# sch.net
KiCad netlist of a schematic drawn in Altium Designer
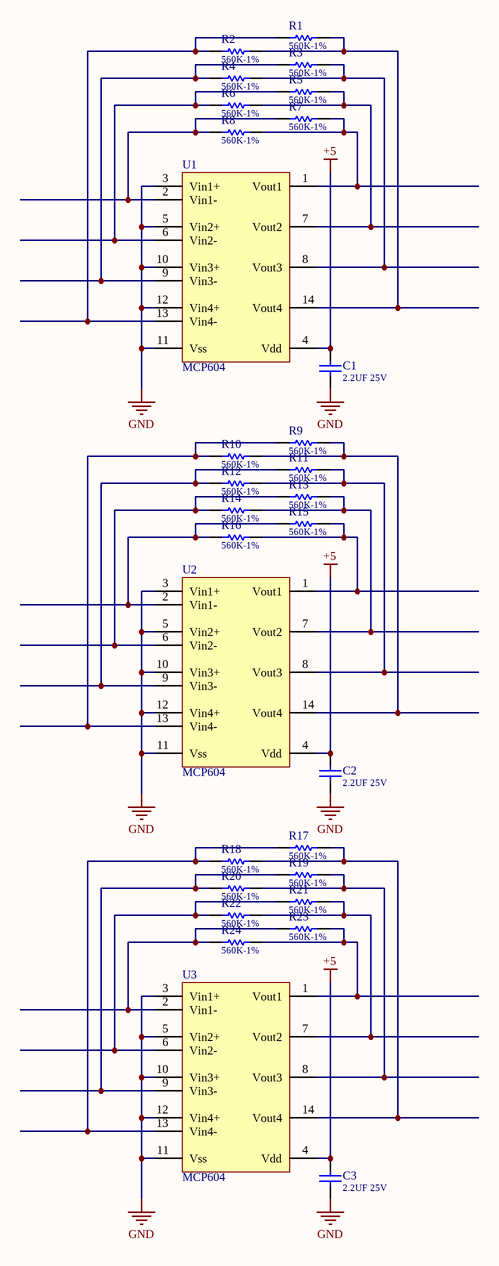
[diagram p0: sch.SchDoc]

(export (version "E")
  (design (tool "Eeschema 10.0.6"))
  (components
    (comp (ref "C1")
      (value "2.2UF 25V")
      (footprint "RC_0603")
      (fields (field (name "PART NUMBER") "CAP_0603_2.2UF 25V") (field (name "MANUFACTURER") "Murata"))
      (libsource (lib "RR_Passive") (part "CAP"))
    )
    (comp (ref "C2")
      (value "2.2UF 25V")
      (footprint "RC_0603")
      (fields (field (name "PART NUMBER") "CAP_0603_2.2UF 25V") (field (name "MANUFACTURER") "Murata"))
      (libsource (lib "RR_Passive") (part "CAP"))
    )
    (comp (ref "C3")
      (value "2.2UF 25V")
      (footprint "RC_0603")
      (fields (field (name "PART NUMBER") "CAP_0603_2.2UF 25V") (field (name "MANUFACTURER") "Murata"))
      (libsource (lib "RR_Passive") (part "CAP"))
    )
    (comp (ref "R1")
      (value "560K-1%")
      (footprint "RR_0603")
      (fields (field (name "MANUFACTURER") "Yageo"))
      (libsource (lib "RozumLibrary") (part "RES"))
    )
    (comp (ref "R2")
      (value "560K-1%")
      (footprint "RR_0603")
      (fields (field (name "MANUFACTURER") "Yageo"))
      (libsource (lib "RozumLibrary") (part "RES"))
    )
    (comp (ref "R3")
      (value "560K-1%")
      (footprint "RR_0603")
      (fields (field (name "MANUFACTURER") "Yageo"))
      (libsource (lib "RozumLibrary") (part "RES"))
    )
    (comp (ref "R4")
      (value "560K-1%")
      (footprint "RR_0603")
      (fields (field (name "MANUFACTURER") "Yageo"))
      (libsource (lib "RozumLibrary") (part "RES"))
    )
    (comp (ref "R5")
      (value "560K-1%")
      (footprint "RR_0603")
      (fields (field (name "MANUFACTURER") "Yageo"))
      (libsource (lib "RozumLibrary") (part "RES"))
    )
    (comp (ref "R6")
      (value "560K-1%")
      (footprint "RR_0603")
      (fields (field (name "MANUFACTURER") "Yageo"))
      (libsource (lib "RozumLibrary") (part "RES"))
    )
    (comp (ref "R7")
      (value "560K-1%")
      (footprint "RR_0603")
      (fields (field (name "MANUFACTURER") "Yageo"))
      (libsource (lib "RozumLibrary") (part "RES"))
    )
    (comp (ref "R8")
      (value "560K-1%")
      (footprint "RR_0603")
      (fields (field (name "MANUFACTURER") "Yageo"))
      (libsource (lib "RozumLibrary") (part "RES"))
    )
    (comp (ref "R9")
      (value "560K-1%")
      (footprint "RR_0603")
      (fields (field (name "MANUFACTURER") "Yageo"))
      (libsource (lib "RozumLibrary") (part "RES"))
    )
    (comp (ref "R10")
      (value "560K-1%")
      (footprint "RR_0603")
      (fields (field (name "MANUFACTURER") "Yageo"))
      (libsource (lib "RozumLibrary") (part "RES"))
    )
    (comp (ref "R11")
      (value "560K-1%")
      (footprint "RR_0603")
      (fields (field (name "MANUFACTURER") "Yageo"))
      (libsource (lib "RozumLibrary") (part "RES"))
    )
    (comp (ref "R12")
      (value "560K-1%")
      (footprint "RR_0603")
      (fields (field (name "MANUFACTURER") "Yageo"))
      (libsource (lib "RozumLibrary") (part "RES"))
    )
    (comp (ref "R13")
      (value "560K-1%")
      (footprint "RR_0603")
      (fields (field (name "MANUFACTURER") "Yageo"))
      (libsource (lib "RozumLibrary") (part "RES"))
    )
    (comp (ref "R14")
      (value "560K-1%")
      (footprint "RR_0603")
      (fields (field (name "MANUFACTURER") "Yageo"))
      (libsource (lib "RozumLibrary") (part "RES"))
    )
    (comp (ref "R15")
      (value "560K-1%")
      (footprint "RR_0603")
      (fields (field (name "MANUFACTURER") "Yageo"))
      (libsource (lib "RozumLibrary") (part "RES"))
    )
    (comp (ref "R16")
      (value "560K-1%")
      (footprint "RR_0603")
      (fields (field (name "MANUFACTURER") "Yageo"))
      (libsource (lib "RozumLibrary") (part "RES"))
    )
    (comp (ref "R17")
      (value "560K-1%")
      (footprint "RR_0603")
      (fields (field (name "MANUFACTURER") "Yageo"))
      (libsource (lib "RozumLibrary") (part "RES"))
    )
    (comp (ref "R18")
      (value "560K-1%")
      (footprint "RR_0603")
      (fields (field (name "MANUFACTURER") "Yageo"))
      (libsource (lib "RozumLibrary") (part "RES"))
    )
    (comp (ref "R19")
      (value "560K-1%")
      (footprint "RR_0603")
      (fields (field (name "MANUFACTURER") "Yageo"))
      (libsource (lib "RozumLibrary") (part "RES"))
    )
    (comp (ref "R20")
      (value "560K-1%")
      (footprint "RR_0603")
      (fields (field (name "MANUFACTURER") "Yageo"))
      (libsource (lib "RozumLibrary") (part "RES"))
    )
    (comp (ref "R21")
      (value "560K-1%")
      (footprint "RR_0603")
      (fields (field (name "MANUFACTURER") "Yageo"))
      (libsource (lib "RozumLibrary") (part "RES"))
    )
    (comp (ref "R22")
      (value "560K-1%")
      (footprint "RR_0603")
      (fields (field (name "MANUFACTURER") "Yageo"))
      (libsource (lib "RozumLibrary") (part "RES"))
    )
    (comp (ref "R23")
      (value "560K-1%")
      (footprint "RR_0603")
      (fields (field (name "MANUFACTURER") "Yageo"))
      (libsource (lib "RozumLibrary") (part "RES"))
    )
    (comp (ref "R24")
      (value "560K-1%")
      (footprint "RR_0603")
      (fields (field (name "MANUFACTURER") "Yageo"))
      (libsource (lib "RozumLibrary") (part "RES"))
    )
    (comp (ref "U1") (value "MCP604") (footprint "RR_SO14") (libsource (lib "lib") (part "MCP604")))
    (comp (ref "U2") (value "MCP604") (footprint "RR_SO14") (libsource (lib "lib") (part "MCP604")))
    (comp (ref "U3") (value "MCP604") (footprint "RR_SO14") (libsource (lib "lib") (part "MCP604")))
  )
  (nets
    (net (code "1") (name "+5") (class "Default")
      (node (ref "C1") (pin "2") (pinfunction "2_2") (pintype "passive"))
      (node (ref "C2") (pin "2") (pinfunction "2_2") (pintype "passive"))
      (node (ref "C3") (pin "2") (pinfunction "2_2") (pintype "passive"))
      (node (ref "U1") (pin "4") (pinfunction "Vdd_4") (pintype "passive"))
      (node (ref "U2") (pin "4") (pinfunction "Vdd_4") (pintype "passive"))
      (node (ref "U3") (pin "4") (pinfunction "Vdd_4") (pintype "passive"))
    )
    (net (code "2") (name "GND") (class "Default")
      (node (ref "C1") (pin "1") (pinfunction "1_1") (pintype "passive"))
      (node (ref "C2") (pin "1") (pinfunction "1_1") (pintype "passive"))
      (node (ref "C3") (pin "1") (pinfunction "1_1") (pintype "passive"))
      (node (ref "U1") (pin "10") (pinfunction "Vin3+_10") (pintype "passive"))
      (node (ref "U1") (pin "11") (pinfunction "Vss_11") (pintype "passive"))
      (node (ref "U1") (pin "12") (pinfunction "Vin4+_12") (pintype "passive"))
      (node (ref "U1") (pin "3") (pinfunction "Vin1+_3") (pintype "passive"))
      (node (ref "U1") (pin "5") (pinfunction "Vin2+_5") (pintype "passive"))
      (node (ref "U2") (pin "10") (pinfunction "Vin3+_10") (pintype "passive"))
      (node (ref "U2") (pin "11") (pinfunction "Vss_11") (pintype "passive"))
      (node (ref "U2") (pin "12") (pinfunction "Vin4+_12") (pintype "passive"))
      (node (ref "U2") (pin "3") (pinfunction "Vin1+_3") (pintype "passive"))
      (node (ref "U2") (pin "5") (pinfunction "Vin2+_5") (pintype "passive"))
      (node (ref "U3") (pin "10") (pinfunction "Vin3+_10") (pintype "passive"))
      (node (ref "U3") (pin "11") (pinfunction "Vss_11") (pintype "passive"))
      (node (ref "U3") (pin "12") (pinfunction "Vin4+_12") (pintype "passive"))
      (node (ref "U3") (pin "3") (pinfunction "Vin1+_3") (pintype "passive"))
      (node (ref "U3") (pin "5") (pinfunction "Vin2+_5") (pintype "passive"))
    )
    (net (code "3") (name "Net-(U1-Vin1-)") (class "Default")
      (node (ref "R7") (pin "2") (pinfunction "2_2") (pintype "passive"))
      (node (ref "R8") (pin "2") (pinfunction "2_2") (pintype "passive"))
      (node (ref "U1") (pin "2") (pinfunction "Vin1-_2") (pintype "passive"))
    )
    (net (code "4") (name "Net-(U1-Vin2-)") (class "Default")
      (node (ref "R5") (pin "2") (pinfunction "2_2") (pintype "passive"))
      (node (ref "R6") (pin "2") (pinfunction "2_2") (pintype "passive"))
      (node (ref "U1") (pin "6") (pinfunction "Vin2-_6") (pintype "passive"))
    )
    (net (code "5") (name "Net-(U1-Vin3-)") (class "Default")
      (node (ref "R3") (pin "2") (pinfunction "2_2") (pintype "passive"))
      (node (ref "R4") (pin "2") (pinfunction "2_2") (pintype "passive"))
      (node (ref "U1") (pin "9") (pinfunction "Vin3-_9") (pintype "passive"))
    )
    (net (code "6") (name "Net-(U1-Vin4-)") (class "Default")
      (node (ref "R1") (pin "2") (pinfunction "2_2") (pintype "passive"))
      (node (ref "R2") (pin "2") (pinfunction "2_2") (pintype "passive"))
      (node (ref "U1") (pin "13") (pinfunction "Vin4-_13") (pintype "passive"))
    )
    (net (code "7") (name "Net-(U1-Vout1)") (class "Default")
      (node (ref "R7") (pin "1") (pinfunction "1_1") (pintype "passive"))
      (node (ref "R8") (pin "1") (pinfunction "1_1") (pintype "passive"))
      (node (ref "U1") (pin "1") (pinfunction "Vout1_1") (pintype "passive"))
    )
    (net (code "8") (name "Net-(U1-Vout2)") (class "Default")
      (node (ref "R5") (pin "1") (pinfunction "1_1") (pintype "passive"))
      (node (ref "R6") (pin "1") (pinfunction "1_1") (pintype "passive"))
      (node (ref "U1") (pin "7") (pinfunction "Vout2_7") (pintype "passive"))
    )
    (net (code "9") (name "Net-(U1-Vout3)") (class "Default")
      (node (ref "R3") (pin "1") (pinfunction "1_1") (pintype "passive"))
      (node (ref "R4") (pin "1") (pinfunction "1_1") (pintype "passive"))
      (node (ref "U1") (pin "8") (pinfunction "Vout3_8") (pintype "passive"))
    )
    (net (code "10") (name "Net-(U1-Vout4)") (class "Default")
      (node (ref "R1") (pin "1") (pinfunction "1_1") (pintype "passive"))
      (node (ref "R2") (pin "1") (pinfunction "1_1") (pintype "passive"))
      (node (ref "U1") (pin "14") (pinfunction "Vout4_14") (pintype "passive"))
    )
    (net (code "11") (name "Net-(U2-Vin1-)") (class "Default")
      (node (ref "R15") (pin "2") (pinfunction "2_2") (pintype "passive"))
      (node (ref "R16") (pin "2") (pinfunction "2_2") (pintype "passive"))
      (node (ref "U2") (pin "2") (pinfunction "Vin1-_2") (pintype "passive"))
    )
    (net (code "12") (name "Net-(U2-Vin2-)") (class "Default")
      (node (ref "R13") (pin "2") (pinfunction "2_2") (pintype "passive"))
      (node (ref "R14") (pin "2") (pinfunction "2_2") (pintype "passive"))
      (node (ref "U2") (pin "6") (pinfunction "Vin2-_6") (pintype "passive"))
    )
    (net (code "13") (name "Net-(U2-Vin3-)") (class "Default")
      (node (ref "R11") (pin "2") (pinfunction "2_2") (pintype "passive"))
      (node (ref "R12") (pin "2") (pinfunction "2_2") (pintype "passive"))
      (node (ref "U2") (pin "9") (pinfunction "Vin3-_9") (pintype "passive"))
    )
    (net (code "14") (name "Net-(U2-Vin4-)") (class "Default")
      (node (ref "R10") (pin "2") (pinfunction "2_2") (pintype "passive"))
      (node (ref "R9") (pin "2") (pinfunction "2_2") (pintype "passive"))
      (node (ref "U2") (pin "13") (pinfunction "Vin4-_13") (pintype "passive"))
    )
    (net (code "15") (name "Net-(U2-Vout1)") (class "Default")
      (node (ref "R15") (pin "1") (pinfunction "1_1") (pintype "passive"))
      (node (ref "R16") (pin "1") (pinfunction "1_1") (pintype "passive"))
      (node (ref "U2") (pin "1") (pinfunction "Vout1_1") (pintype "passive"))
    )
    (net (code "16") (name "Net-(U2-Vout2)") (class "Default")
      (node (ref "R13") (pin "1") (pinfunction "1_1") (pintype "passive"))
      (node (ref "R14") (pin "1") (pinfunction "1_1") (pintype "passive"))
      (node (ref "U2") (pin "7") (pinfunction "Vout2_7") (pintype "passive"))
    )
    (net (code "17") (name "Net-(U2-Vout3)") (class "Default")
      (node (ref "R11") (pin "1") (pinfunction "1_1") (pintype "passive"))
      (node (ref "R12") (pin "1") (pinfunction "1_1") (pintype "passive"))
      (node (ref "U2") (pin "8") (pinfunction "Vout3_8") (pintype "passive"))
    )
    (net (code "18") (name "Net-(U2-Vout4)") (class "Default")
      (node (ref "R10") (pin "1") (pinfunction "1_1") (pintype "passive"))
      (node (ref "R9") (pin "1") (pinfunction "1_1") (pintype "passive"))
      (node (ref "U2") (pin "14") (pinfunction "Vout4_14") (pintype "passive"))
    )
    (net (code "19") (name "Net-(U3-Vin1-)") (class "Default")
      (node (ref "R23") (pin "2") (pinfunction "2_2") (pintype "passive"))
      (node (ref "R24") (pin "2") (pinfunction "2_2") (pintype "passive"))
      (node (ref "U3") (pin "2") (pinfunction "Vin1-_2") (pintype "passive"))
    )
    (net (code "20") (name "Net-(U3-Vin2-)") (class "Default")
      (node (ref "R21") (pin "2") (pinfunction "2_2") (pintype "passive"))
      (node (ref "R22") (pin "2") (pinfunction "2_2") (pintype "passive"))
      (node (ref "U3") (pin "6") (pinfunction "Vin2-_6") (pintype "passive"))
    )
    (net (code "21") (name "Net-(U3-Vin3-)") (class "Default")
      (node (ref "R19") (pin "2") (pinfunction "2_2") (pintype "passive"))
      (node (ref "R20") (pin "2") (pinfunction "2_2") (pintype "passive"))
      (node (ref "U3") (pin "9") (pinfunction "Vin3-_9") (pintype "passive"))
    )
    (net (code "22") (name "Net-(U3-Vin4-)") (class "Default")
      (node (ref "R17") (pin "2") (pinfunction "2_2") (pintype "passive"))
      (node (ref "R18") (pin "2") (pinfunction "2_2") (pintype "passive"))
      (node (ref "U3") (pin "13") (pinfunction "Vin4-_13") (pintype "passive"))
    )
    (net (code "23") (name "Net-(U3-Vout1)") (class "Default")
      (node (ref "R23") (pin "1") (pinfunction "1_1") (pintype "passive"))
      (node (ref "R24") (pin "1") (pinfunction "1_1") (pintype "passive"))
      (node (ref "U3") (pin "1") (pinfunction "Vout1_1") (pintype "passive"))
    )
    (net (code "24") (name "Net-(U3-Vout2)") (class "Default")
      (node (ref "R21") (pin "1") (pinfunction "1_1") (pintype "passive"))
      (node (ref "R22") (pin "1") (pinfunction "1_1") (pintype "passive"))
      (node (ref "U3") (pin "7") (pinfunction "Vout2_7") (pintype "passive"))
    )
    (net (code "25") (name "Net-(U3-Vout3)") (class "Default")
      (node (ref "R19") (pin "1") (pinfunction "1_1") (pintype "passive"))
      (node (ref "R20") (pin "1") (pinfunction "1_1") (pintype "passive"))
      (node (ref "U3") (pin "8") (pinfunction "Vout3_8") (pintype "passive"))
    )
    (net (code "26") (name "Net-(U3-Vout4)") (class "Default")
      (node (ref "R17") (pin "1") (pinfunction "1_1") (pintype "passive"))
      (node (ref "R18") (pin "1") (pinfunction "1_1") (pintype "passive"))
      (node (ref "U3") (pin "14") (pinfunction "Vout4_14") (pintype "passive"))
    )
  )
)
